# pentabug_v2_1.net
KiCad netlist of a schematic drawn in EAGLE
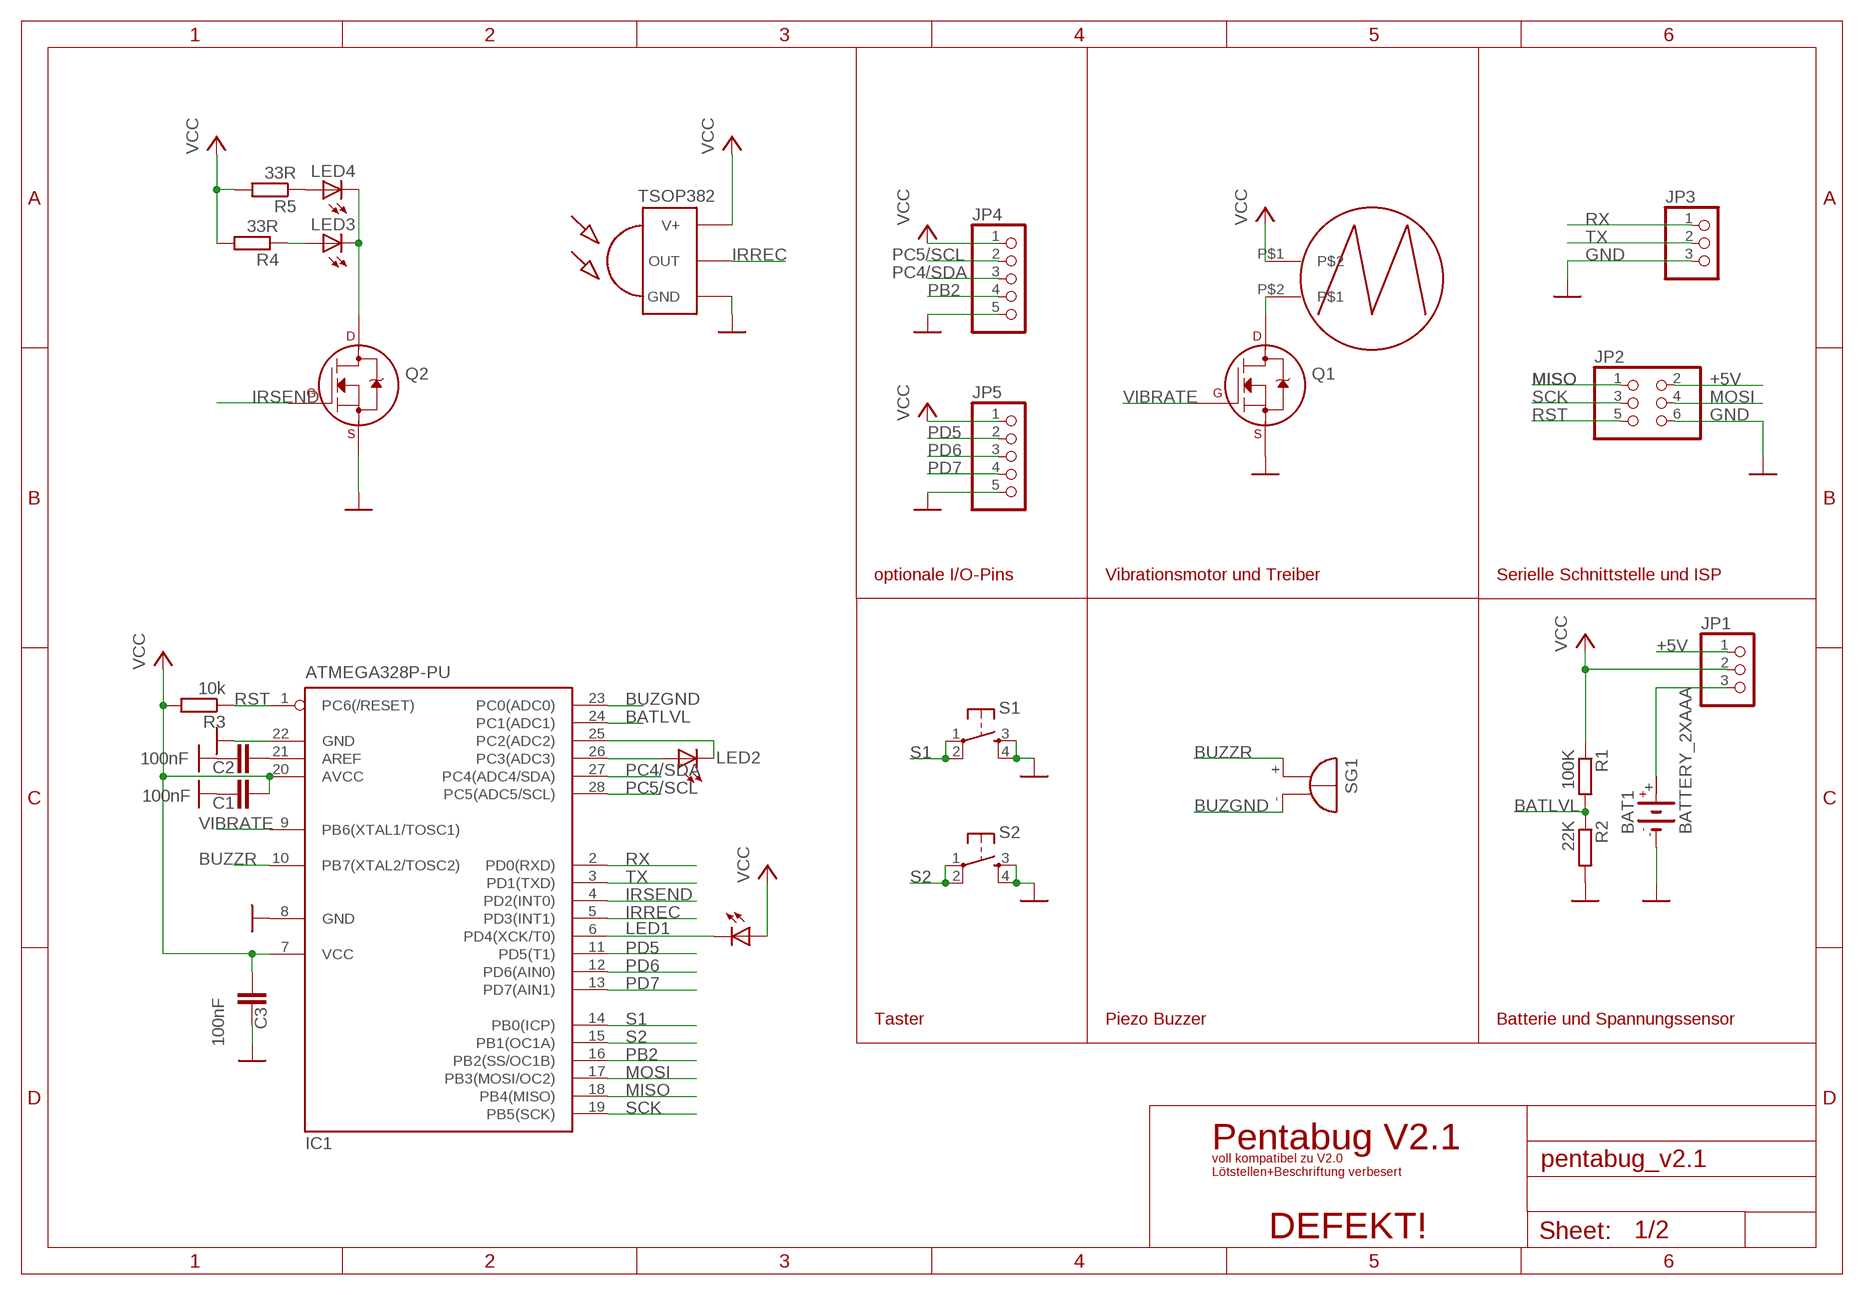
[diagram p0: schematic, sheet 1]

(export (version "E")
  (design (tool "Eeschema 10.0.6"))
  (components
    (comp (ref "BAT1")
      (value "BATTERY_2XAAA")
      (footprint "eagle-import:BATTERY_2XAAA_SMALLPINS")
      (libsource (lib "eagle-import") (part "BATTERY_2XAAA"))
    )
    (comp (ref "C1")
      (value "100nF")
      (footprint "eagle-import:C025-024X044")
      (libsource (lib "eagle-import") (part "C-EU025-024X044"))
    )
    (comp (ref "C2")
      (value "100nF")
      (footprint "eagle-import:C025-024X044")
      (libsource (lib "eagle-import") (part "C-EU025-024X044"))
    )
    (comp (ref "C3")
      (value "100nF")
      (footprint "eagle-import:C025-024X044")
      (libsource (lib "eagle-import") (part "C-EU025-024X044"))
    )
    (comp (ref "IC1")
      (value "ATMEGA328P-PU")
      (footprint "eagle-import:DIL28-3")
      (libsource (lib "eagle-import") (part "MEGA8-P"))
    )
    (comp (ref "IR")
      (value "TSOP382")
      (footprint "eagle-import:TSOP382")
      (libsource (lib "eagle-import") (part "TSOP382"))
    )
    (comp (ref "JP1")
      (value "PINHD-1X3")
      (footprint "eagle-import:1X03")
      (libsource (lib "eagle-import") (part "PINHD-1X3"))
    )
    (comp (ref "JP2")
      (value "PINHD-2X3")
      (footprint "eagle-import:2X03")
      (libsource (lib "eagle-import") (part "PINHD-2X3"))
    )
    (comp (ref "JP3")
      (value "PINHD-1X3")
      (footprint "eagle-import:1X03")
      (libsource (lib "eagle-import") (part "PINHD-1X3"))
    )
    (comp (ref "JP4")
      (value "PINHD-1X5")
      (footprint "eagle-import:1X05")
      (libsource (lib "eagle-import") (part "PINHD-1X5"))
    )
    (comp (ref "JP5")
      (value "PINHD-1X5")
      (footprint "eagle-import:1X05")
      (libsource (lib "eagle-import") (part "PINHD-1X5"))
    )
    (comp (ref "LED1")
      (value "LED5MM")
      (footprint "eagle-import:LED5MM")
      (libsource (lib "eagle-import") (part "LED5MM"))
    )
    (comp (ref "LED2")
      (value "LED5MM")
      (footprint "eagle-import:LED5MM")
      (libsource (lib "eagle-import") (part "LED5MM"))
    )
    (comp (ref "LED3")
      (value "LED3MM")
      (footprint "eagle-import:LED3MM")
      (libsource (lib "eagle-import") (part "LED3MM"))
    )
    (comp (ref "LED4")
      (value "LED3MM")
      (footprint "eagle-import:LED3MM")
      (libsource (lib "eagle-import") (part "LED3MM"))
    )
    (comp (ref "Q1")
      (value "2N7000")
      (footprint "eagle-import:TO92-")
      (libsource (lib "eagle-import") (part "2N7000"))
    )
    (comp (ref "Q2")
      (value "2N7000")
      (footprint "eagle-import:TO92-")
      (libsource (lib "eagle-import") (part "2N7000"))
    )
    (comp (ref "R1")
      (value "100K")
      (footprint "eagle-import:0207_10")
      (libsource (lib "eagle-import") (part "R-EU_EASY-SOLDER0207/10_EASY-SOLDER"))
    )
    (comp (ref "R2")
      (value "22K")
      (footprint "eagle-import:0207_10")
      (libsource (lib "eagle-import") (part "R-EU_EASY-SOLDER0207/10_EASY-SOLDER"))
    )
    (comp (ref "R3")
      (value "10k")
      (footprint "eagle-import:0207_10")
      (libsource (lib "eagle-import") (part "R-EU_EASY-SOLDER0207/10_EASY-SOLDER"))
    )
    (comp (ref "R4")
      (value "33R")
      (footprint "eagle-import:0207_10")
      (libsource (lib "eagle-import") (part "R-EU_EASY-SOLDER0207/10_EASY-SOLDER"))
    )
    (comp (ref "R5")
      (value "33R")
      (footprint "eagle-import:0207_10")
      (libsource (lib "eagle-import") (part "R-EU_EASY-SOLDER0207/10_EASY-SOLDER"))
    )
    (comp (ref "S1")
      (value "TAC_SWITCHPTH")
      (footprint "eagle-import:TACTILE-PTH")
      (libsource (lib "eagle-import") (part "TAC_SWITCHPTH"))
    )
    (comp (ref "S2")
      (value "TAC_SWITCHPTH")
      (footprint "eagle-import:TACTILE-PTH")
      (libsource (lib "eagle-import") (part "TAC_SWITCHPTH"))
    )
    (comp (ref "SG1")
      (value "MULTIBUZZRTDKBUZZR")
      (footprint "eagle-import:BUZZRTDK")
      (libsource (lib "eagle-import") (part "MULTIBUZZRTDKBUZZR"))
    )
    (comp (ref "U$1")
      (value "VIBRAMOTOR")
      (footprint "eagle-import:LA4-432")
      (libsource (lib "eagle-import") (part "VIBRAMOTOR"))
    )
  )
  (nets
    (net (code "1") (name "+5V") (class "Default")
      (node (ref "JP1") (pin "1") (pinfunction "1_1") (pintype "passive"))
      (node (ref "JP2") (pin "2") (pinfunction "2_2") (pintype "passive"))
    )
    (net (code "2") (name "BATLVL") (class "Default")
      (node (ref "IC1") (pin "24") (pinfunction "PC1(ADC1)_24") (pintype "bidirectional"))
      (node (ref "R1") (pin "2") (pinfunction "2_2") (pintype "passive"))
      (node (ref "R2") (pin "1") (pinfunction "1_1") (pintype "passive"))
    )
    (net (code "3") (name "BUZGND") (class "Default")
      (node (ref "IC1") (pin "23") (pinfunction "PC0(ADC0)_23") (pintype "bidirectional"))
      (node (ref "SG1") (pin "-") (pinfunction "-_-") (pintype "passive"))
    )
    (net (code "4") (name "BUZZR") (class "Default")
      (node (ref "IC1") (pin "10") (pinfunction "PB7(XTAL2/TOSC2)_10") (pintype "bidirectional"))
      (node (ref "SG1") (pin "+") (pinfunction "+_+") (pintype "passive"))
    )
    (net (code "5") (name "GND") (class "Default")
      (node (ref "BAT1") (pin "-") (pinfunction "-_-") (pintype "passive"))
      (node (ref "C1") (pin "1") (pinfunction "1_1") (pintype "passive"))
      (node (ref "C2") (pin "1") (pinfunction "1_1") (pintype "passive"))
      (node (ref "C3") (pin "1") (pinfunction "1_1") (pintype "passive"))
      (node (ref "IC1") (pin "22") (pinfunction "GND_22") (pintype "power_in"))
      (node (ref "IC1") (pin "8") (pinfunction "GND_8") (pintype "power_in"))
      (node (ref "IR") (pin "GND") (pinfunction "GND_GND") (pintype "bidirectional"))
      (node (ref "JP2") (pin "6") (pinfunction "6_6") (pintype "passive"))
      (node (ref "JP3") (pin "3") (pinfunction "3_3") (pintype "passive"))
      (node (ref "JP4") (pin "5") (pinfunction "5_5") (pintype "passive"))
      (node (ref "JP5") (pin "5") (pinfunction "5_5") (pintype "passive"))
      (node (ref "Q1") (pin "1") (pinfunction "S_1") (pintype "bidirectional"))
      (node (ref "Q2") (pin "1") (pinfunction "S_1") (pintype "bidirectional"))
      (node (ref "R2") (pin "2") (pinfunction "2_2") (pintype "passive"))
      (node (ref "S1") (pin "3") (pinfunction "3_3") (pintype "passive"))
      (node (ref "S1") (pin "4") (pinfunction "4_4") (pintype "passive"))
      (node (ref "S2") (pin "3") (pinfunction "3_3") (pintype "passive"))
      (node (ref "S2") (pin "4") (pinfunction "4_4") (pintype "passive"))
    )
    (net (code "6") (name "IRREC") (class "Default")
      (node (ref "IC1") (pin "5") (pinfunction "PD3(INT1)_5") (pintype "bidirectional"))
      (node (ref "IR") (pin "OUT") (pinfunction "OUT_OUT") (pintype "bidirectional"))
    )
    (net (code "7") (name "IRSEND") (class "Default")
      (node (ref "IC1") (pin "4") (pinfunction "PD2(INT0)_4") (pintype "bidirectional"))
      (node (ref "Q2") (pin "2") (pinfunction "G_2") (pintype "tri_state"))
    )
    (net (code "8") (name "MISO") (class "Default")
      (node (ref "IC1") (pin "18") (pinfunction "PB4(MISO)_18") (pintype "bidirectional"))
      (node (ref "JP2") (pin "1") (pinfunction "1_1") (pintype "passive"))
    )
    (net (code "9") (name "MOSI") (class "Default")
      (node (ref "IC1") (pin "17") (pinfunction "PB3(MOSI/OC2)_17") (pintype "bidirectional"))
      (node (ref "JP2") (pin "4") (pinfunction "4_4") (pintype "passive"))
    )
    (net (code "10") (name "Net-(BAT1-Pad+)") (class "Default")
      (node (ref "BAT1") (pin "+") (pinfunction "+_+") (pintype "passive"))
      (node (ref "JP1") (pin "3") (pinfunction "3_3") (pintype "passive"))
    )
    (net (code "11") (name "Net-(IC1-AREF)") (class "Default")
      (node (ref "C2") (pin "2") (pinfunction "2_2") (pintype "passive"))
      (node (ref "IC1") (pin "21") (pinfunction "AREF_21") (pintype "passive"))
    )
    (net (code "12") (name "Net-(IC1-PC2(ADC2))") (class "Default")
      (node (ref "IC1") (pin "25") (pinfunction "PC2(ADC2)_25") (pintype "bidirectional"))
      (node (ref "LED2") (pin "K") (pinfunction "C_K") (pintype "passive"))
    )
    (net (code "13") (name "Net-(IC1-PC3(ADC3))") (class "Default")
      (node (ref "IC1") (pin "26") (pinfunction "PC3(ADC3)_26") (pintype "bidirectional"))
      (node (ref "LED2") (pin "A") (pinfunction "A_A") (pintype "passive"))
    )
    (net (code "14") (name "Net-(IC1-PD4(XCK{slash}T0))") (class "Default")
      (node (ref "IC1") (pin "6") (pinfunction "PD4(XCK/T0)_6") (pintype "bidirectional"))
      (node (ref "LED1") (pin "K") (pinfunction "C_K") (pintype "passive"))
    )
    (net (code "15") (name "Net-(LED3-C)") (class "Default")
      (node (ref "LED3") (pin "K") (pinfunction "C_K") (pintype "passive"))
      (node (ref "LED4") (pin "K") (pinfunction "C_K") (pintype "passive"))
      (node (ref "Q2") (pin "3") (pinfunction "D_3") (pintype "bidirectional"))
    )
    (net (code "16") (name "Net-(LED3-PadA)") (class "Default")
      (node (ref "LED3") (pin "A") (pinfunction "A_A") (pintype "passive"))
      (node (ref "R4") (pin "1") (pinfunction "1_1") (pintype "passive"))
    )
    (net (code "17") (name "Net-(LED4-PadA)") (class "Default")
      (node (ref "LED4") (pin "A") (pinfunction "A_A") (pintype "passive"))
      (node (ref "R5") (pin "1") (pinfunction "1_1") (pintype "passive"))
    )
    (net (code "18") (name "Net-(Q1-D)") (class "Default")
      (node (ref "Q1") (pin "3") (pinfunction "D_3") (pintype "bidirectional"))
      (node (ref "U$1") (pin "P$2") (pinfunction "P$1_P$2") (pintype "power_in"))
    )
    (net (code "19") (name "PB2") (class "Default")
      (node (ref "IC1") (pin "16") (pinfunction "PB2(SS/OC1B)_16") (pintype "bidirectional"))
      (node (ref "JP4") (pin "4") (pinfunction "4_4") (pintype "passive"))
    )
    (net (code "20") (name "PC4{slash}SDA") (class "Default")
      (node (ref "IC1") (pin "27") (pinfunction "PC4(ADC4/SDA)_27") (pintype "bidirectional"))
      (node (ref "JP4") (pin "3") (pinfunction "3_3") (pintype "passive"))
    )
    (net (code "21") (name "PC5{slash}SCL") (class "Default")
      (node (ref "IC1") (pin "28") (pinfunction "PC5(ADC5/SCL)_28") (pintype "bidirectional"))
      (node (ref "JP4") (pin "2") (pinfunction "2_2") (pintype "passive"))
    )
    (net (code "22") (name "PD5") (class "Default")
      (node (ref "IC1") (pin "11") (pinfunction "PD5(T1)_11") (pintype "bidirectional"))
      (node (ref "JP5") (pin "2") (pinfunction "2_2") (pintype "passive"))
    )
    (net (code "23") (name "PD6") (class "Default")
      (node (ref "IC1") (pin "12") (pinfunction "PD6(AIN0)_12") (pintype "bidirectional"))
      (node (ref "JP5") (pin "3") (pinfunction "3_3") (pintype "passive"))
    )
    (net (code "24") (name "PD7") (class "Default")
      (node (ref "IC1") (pin "13") (pinfunction "PD7(AIN1)_13") (pintype "bidirectional"))
      (node (ref "JP5") (pin "4") (pinfunction "4_4") (pintype "passive"))
    )
    (net (code "25") (name "RST") (class "Default")
      (node (ref "IC1") (pin "1") (pinfunction "PC6(/RESET)_1") (pintype "bidirectional"))
      (node (ref "JP2") (pin "5") (pinfunction "5_5") (pintype "passive"))
      (node (ref "R3") (pin "1") (pinfunction "1_1") (pintype "passive"))
    )
    (net (code "26") (name "RX") (class "Default")
      (node (ref "IC1") (pin "2") (pinfunction "PD0(RXD)_2") (pintype "bidirectional"))
      (node (ref "JP3") (pin "1") (pinfunction "1_1") (pintype "passive"))
    )
    (net (code "27") (name "S1") (class "Default")
      (node (ref "IC1") (pin "14") (pinfunction "PB0(ICP)_14") (pintype "bidirectional"))
      (node (ref "S1") (pin "1") (pinfunction "1_1") (pintype "passive"))
      (node (ref "S1") (pin "2") (pinfunction "2_2") (pintype "passive"))
    )
    (net (code "28") (name "S2") (class "Default")
      (node (ref "IC1") (pin "15") (pinfunction "PB1(OC1A)_15") (pintype "bidirectional"))
      (node (ref "S2") (pin "1") (pinfunction "1_1") (pintype "passive"))
      (node (ref "S2") (pin "2") (pinfunction "2_2") (pintype "passive"))
    )
    (net (code "29") (name "SCK") (class "Default")
      (node (ref "IC1") (pin "19") (pinfunction "PB5(SCK)_19") (pintype "bidirectional"))
      (node (ref "JP2") (pin "3") (pinfunction "3_3") (pintype "passive"))
    )
    (net (code "30") (name "TX") (class "Default")
      (node (ref "IC1") (pin "3") (pinfunction "PD1(TXD)_3") (pintype "bidirectional"))
      (node (ref "JP3") (pin "2") (pinfunction "2_2") (pintype "passive"))
    )
    (net (code "31") (name "VCC") (class "Default")
      (node (ref "C1") (pin "2") (pinfunction "2_2") (pintype "passive"))
      (node (ref "C3") (pin "2") (pinfunction "2_2") (pintype "passive"))
      (node (ref "IC1") (pin "20") (pinfunction "AVCC_20") (pintype "power_in"))
      (node (ref "IC1") (pin "7") (pinfunction "VCC_7") (pintype "power_in"))
      (node (ref "IR") (pin "VCC") (pinfunction "V+_VCC") (pintype "bidirectional"))
      (node (ref "JP1") (pin "2") (pinfunction "2_2") (pintype "passive"))
      (node (ref "JP4") (pin "1") (pinfunction "1_1") (pintype "passive"))
      (node (ref "JP5") (pin "1") (pinfunction "1_1") (pintype "passive"))
      (node (ref "LED1") (pin "A") (pinfunction "A_A") (pintype "passive"))
      (node (ref "R1") (pin "1") (pinfunction "1_1") (pintype "passive"))
      (node (ref "R3") (pin "2") (pinfunction "2_2") (pintype "passive"))
      (node (ref "R4") (pin "2") (pinfunction "2_2") (pintype "passive"))
      (node (ref "R5") (pin "2") (pinfunction "2_2") (pintype "passive"))
      (node (ref "U$1") (pin "P$1") (pinfunction "P$2_P$1") (pintype "power_in"))
    )
    (net (code "32") (name "VIBRATE") (class "Default")
      (node (ref "IC1") (pin "9") (pinfunction "PB6(XTAL1/TOSC1)_9") (pintype "bidirectional"))
      (node (ref "Q1") (pin "2") (pinfunction "G_2") (pintype "tri_state"))
    )
  )
)
